# SCH_Business-Card-Yannik_2025-03-12.net
KiCad netlist of a schematic drawn in EasyEDA
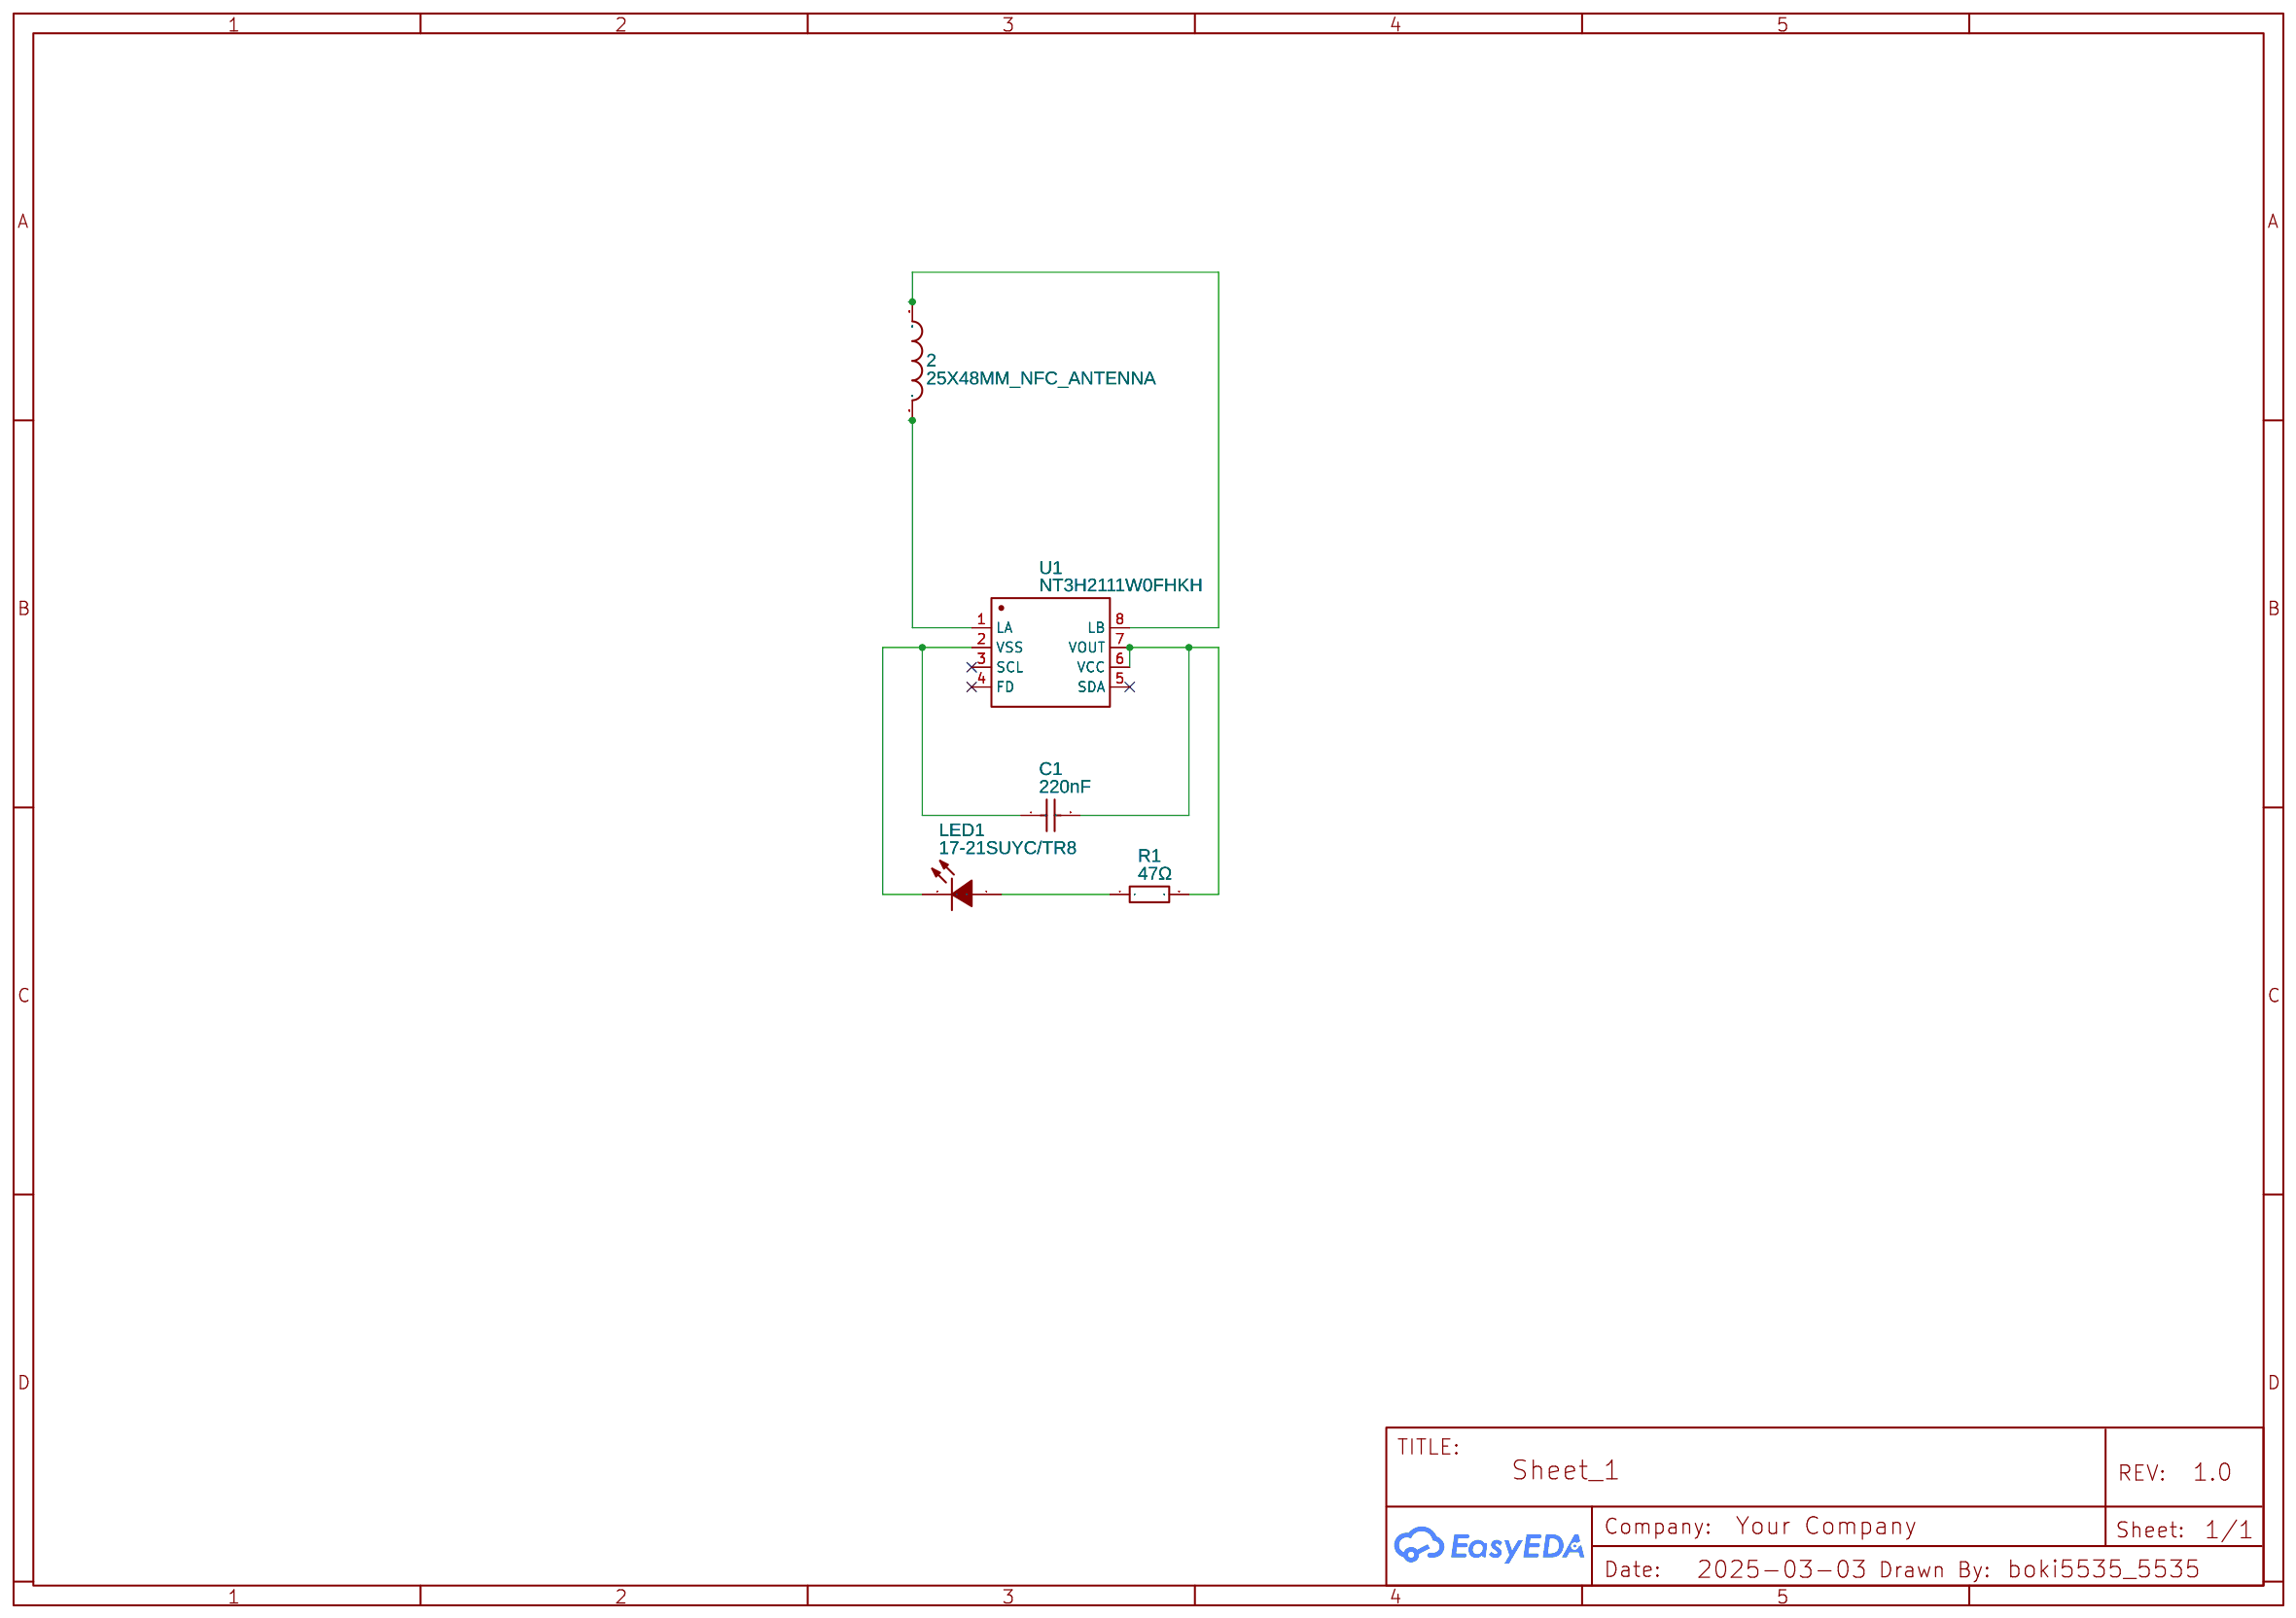
[diagram p0: schematic sheet]

(export (version "E")
  (design (tool "Eeschema 10.0.6"))
  (components
    (comp (ref "2") (value "25X48MM_NFC_ANTENNA") (libsource (lib "") (part "25X48MM_NFC_ANTENNA")))
    (comp (ref "C1")
      (value "220nF")
      (fields
        (field (name "Manufacturer Part") "CL10B224KA8NNNC")
        (field (name "Manufacturer") "SAMSUNG(三星)")
      )
      (libsource (lib "") (part "CL10B224KA8NNNC"))
    )
    (comp (ref "LED1")
      (value "17-21SUYC/TR8")
      (fields (field (name "Manufacturer Part") "KT-0805黄灯") (field (name "Manufacturer") "KENTO"))
      (libsource (lib "") (part "17-21SUYC/TR8"))
    )
    (comp (ref "R1")
      (value "47Ω")
      (fields
        (field (name "Manufacturer Part") "0603WAF470JT5E")
        (field (name "Manufacturer") "UNI-ROYAL(厚声)")
      )
      (libsource (lib "") (part "0603WAF470JT5E"))
    )
    (comp (ref "U1")
      (value "NT3H2111W0FHKH")
      (fields (field (name "Manufacturer") "NXP(恩智浦)"))
      (libsource (lib "") (part "NT3H2111W0FHKH"))
    )
  )
  (nets
    (net (code "1") (name "Net-(LED1-+)") (class "Default")
      (node (ref "LED1") (pin "1") (pinfunction "+_1") (pintype "unspecified"))
      (node (ref "R1") (pin "1") (pinfunction "1_1") (pintype "input"))
    )
    (net (code "2") (name "Net-(LED1--)") (class "Default")
      (node (ref "C1") (pin "1") (pinfunction "1_1") (pintype "input"))
      (node (ref "LED1") (pin "2") (pinfunction "-_2") (pintype "unspecified"))
      (node (ref "U1") (pin "2") (pinfunction "VSS_2") (pintype "unspecified"))
    )
    (net (code "3") (name "Net-(U1-LA)") (class "Default")
      (node (ref "2") (pin "P$2") (pinfunction "P$2_P$2") (pintype "bidirectional"))
      (node (ref "U1") (pin "1") (pinfunction "LA_1") (pintype "unspecified"))
    )
    (net (code "4") (name "Net-(U1-LB)") (class "Default")
      (node (ref "2") (pin "P$1") (pinfunction "P$1_P$1") (pintype "bidirectional"))
      (node (ref "U1") (pin "8") (pinfunction "LB_8") (pintype "unspecified"))
    )
    (net (code "5") (name "Net-(U1-VCC)") (class "Default")
      (node (ref "C1") (pin "2") (pinfunction "2_2") (pintype "input"))
      (node (ref "R1") (pin "2") (pinfunction "2_2") (pintype "input"))
      (node (ref "U1") (pin "6") (pinfunction "VCC_6") (pintype "unspecified"))
      (node (ref "U1") (pin "7") (pinfunction "VOUT_7") (pintype "unspecified"))
    )
    (net (code "6") (name "unconnected-(U1-FD-Pad4)") (class "Default")
      (node (ref "U1") (pin "4") (pinfunction "FD_4") (pintype "unspecified+no_connect"))
    )
    (net (code "7") (name "unconnected-(U1-SCL-Pad3)") (class "Default")
      (node (ref "U1") (pin "3") (pinfunction "SCL_3") (pintype "unspecified+no_connect"))
    )
    (net (code "8") (name "unconnected-(U1-SDA-Pad5)") (class "Default")
      (node (ref "U1") (pin "5") (pinfunction "SDA_5") (pintype "unspecified+no_connect"))
    )
  )
)
